# MCU.net
KiCad netlist of a schematic drawn in Altium Designer
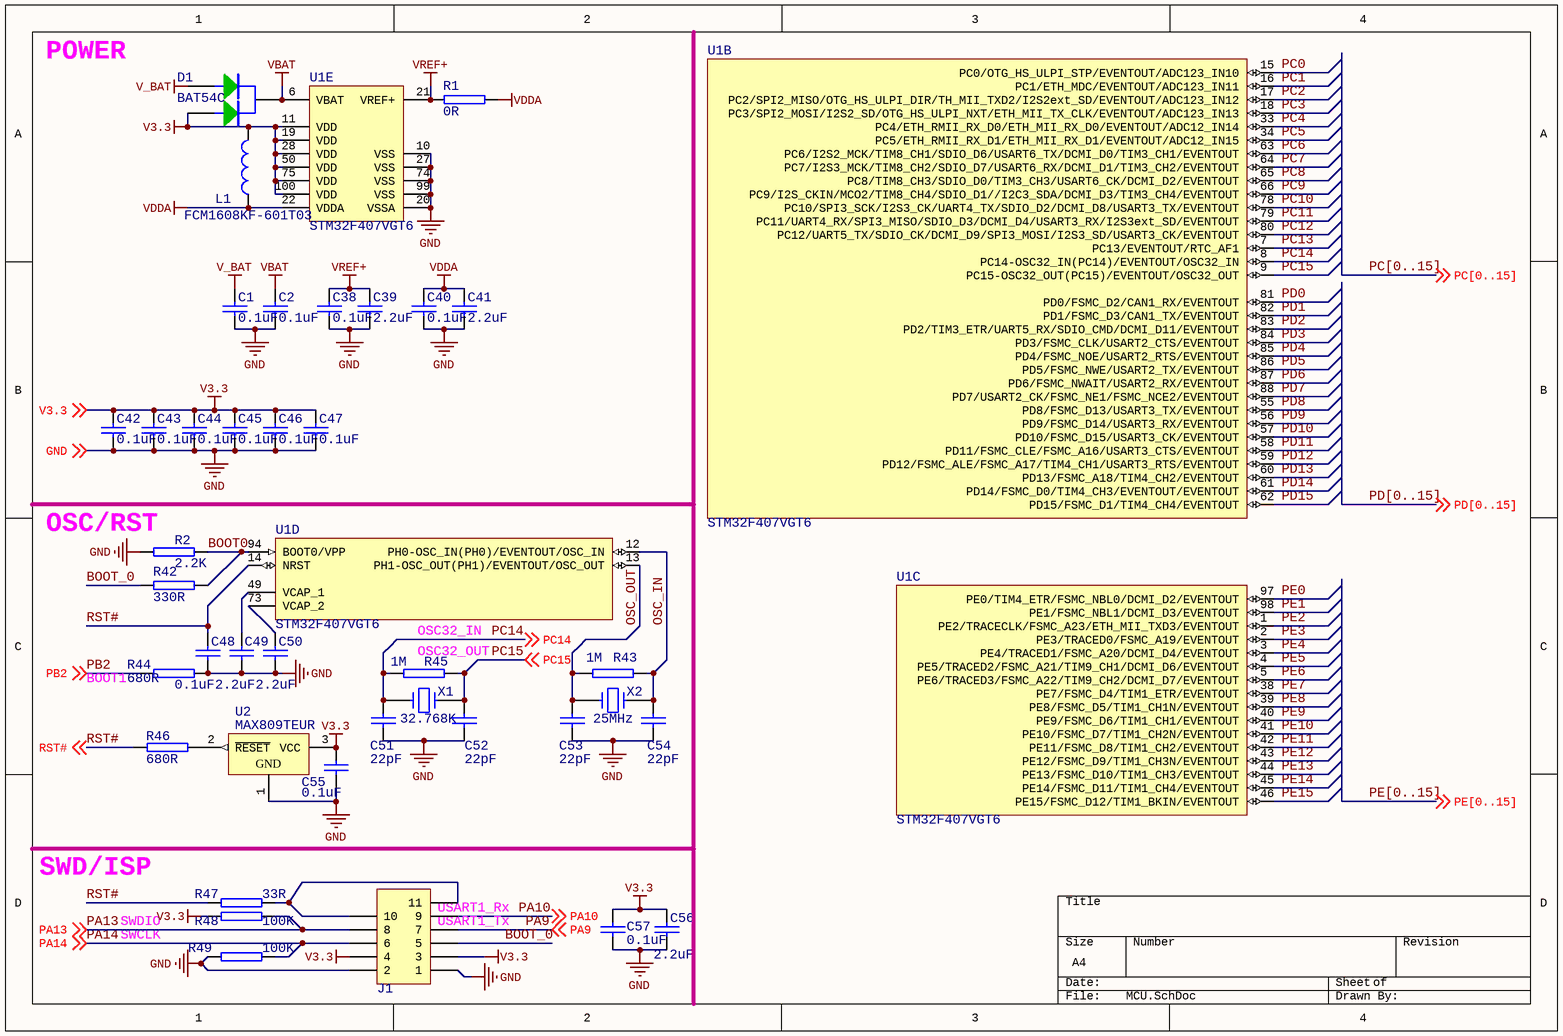
[diagram p0: MCU.SchDoc]

(export (version "E")
  (design (tool "Eeschema 10.0.6"))
  (components
    (comp (ref "C1")
      (value "0.1uF")
      (footprint "C1608(0603)")
      (description "Capacitor")
      (libsource (lib "input") (part "CAP"))
    )
    (comp (ref "C2")
      (value "0.1uF")
      (footprint "C1608(0603)")
      (description "Capacitor")
      (libsource (lib "input") (part "CAP"))
    )
    (comp (ref "C38")
      (value "0.1uF")
      (footprint "C1608(0603)")
      (description "Capacitor")
      (libsource (lib "input") (part "CAP"))
    )
    (comp (ref "C39")
      (value "2.2uF")
      (footprint "C1608(0603)")
      (description "Capacitor")
      (libsource (lib "input") (part "CAP"))
    )
    (comp (ref "C40")
      (value "0.1uF")
      (footprint "C1608(0603)")
      (description "Capacitor")
      (libsource (lib "input") (part "CAP"))
    )
    (comp (ref "C41")
      (value "2.2uF")
      (footprint "C1608(0603)")
      (description "Capacitor")
      (libsource (lib "input") (part "CAP"))
    )
    (comp (ref "C42")
      (value "0.1uF")
      (footprint "C1608(0603)")
      (description "Capacitor")
      (libsource (lib "input") (part "CAP"))
    )
    (comp (ref "C43")
      (value "0.1uF")
      (footprint "C1608(0603)")
      (description "Capacitor")
      (libsource (lib "input") (part "CAP"))
    )
    (comp (ref "C44")
      (value "0.1uF")
      (footprint "C1608(0603)")
      (description "Capacitor")
      (libsource (lib "input") (part "CAP"))
    )
    (comp (ref "C45")
      (value "0.1uF")
      (footprint "C1608(0603)")
      (description "Capacitor")
      (libsource (lib "input") (part "CAP"))
    )
    (comp (ref "C46")
      (value "0.1uF")
      (footprint "C1608(0603)")
      (description "Capacitor")
      (libsource (lib "input") (part "CAP"))
    )
    (comp (ref "C47")
      (value "0.1uF")
      (footprint "C1608(0603)")
      (description "Capacitor")
      (libsource (lib "input") (part "CAP"))
    )
    (comp (ref "C48")
      (value "0.1uF")
      (footprint "C1608(0603)")
      (description "Capacitor")
      (libsource (lib "input") (part "CAP"))
    )
    (comp (ref "C49")
      (value "2.2uF")
      (footprint "C1608(0603)")
      (description "Capacitor")
      (libsource (lib "input") (part "CAP"))
    )
    (comp (ref "C50")
      (value "2.2uF")
      (footprint "C1608(0603)")
      (description "Capacitor")
      (libsource (lib "input") (part "CAP"))
    )
    (comp (ref "C51")
      (value "22pF")
      (footprint "C1608(0603)")
      (description "Capacitor")
      (libsource (lib "input") (part "CAP"))
    )
    (comp (ref "C52")
      (value "22pF")
      (footprint "C1608(0603)")
      (description "Capacitor")
      (libsource (lib "input") (part "CAP"))
    )
    (comp (ref "C53")
      (value "22pF")
      (footprint "C1608(0603)")
      (description "Capacitor")
      (libsource (lib "input") (part "CAP"))
    )
    (comp (ref "C54")
      (value "22pF")
      (footprint "C1608(0603)")
      (description "Capacitor")
      (libsource (lib "input") (part "CAP"))
    )
    (comp (ref "C55")
      (value "0.1uF")
      (footprint "C1608(0603)")
      (description "Capacitor")
      (libsource (lib "input") (part "CAP"))
    )
    (comp (ref "C56")
      (value "2.2uF")
      (footprint "C1608(0603)")
      (description "Capacitor")
      (libsource (lib "input") (part "CAP"))
    )
    (comp (ref "C57")
      (value "0.1uF")
      (footprint "C1608(0603)")
      (description "Capacitor")
      (libsource (lib "input") (part "CAP"))
    )
    (comp (ref "D1")
      (value "BAT54C")
      (footprint "SOT23-3_N")
      (libsource (lib "Mini-STM32F4x9IG-DK-B-SCH") (part "BAT54C"))
    )
    (comp (ref "J1")
      (value "H2.54 6X2")
      (footprint "HDR2X6H")
      (description "Header, 6-Pin, Dual row")
      (fields (field (name "PUBLISHER") "Altium Limited"))
      (libsource (lib "Miscellaneous Connectors") (part "Header 6X2"))
    )
    (comp (ref "L1")
      (value "FCM1608KF-601T03")
      (footprint "R1608(0603)")
      (description "Inductor")
      (fields (field (name "PUBLISHER") "Altium Limited"))
      (libsource (lib "Miscellaneous Devices") (part "Inductor"))
    )
    (comp (ref "R1") (value "0R") (footprint "R1608(0603)") (libsource (lib "motor") (part "R")))
    (comp (ref "R2") (value "2.2K") (footprint "R1608(0603)") (libsource (lib "motor") (part "R")))
    (comp (ref "R42") (value "330R") (footprint "R1608(0603)") (libsource (lib "motor") (part "R")))
    (comp (ref "R43") (value "1M") (footprint "R1608(0603)") (libsource (lib "motor") (part "R")))
    (comp (ref "R44") (value "680R") (footprint "R1608(0603)") (libsource (lib "motor") (part "R")))
    (comp (ref "R45") (value "1M") (footprint "R1608(0603)") (libsource (lib "motor") (part "R")))
    (comp (ref "R46") (value "680R") (footprint "R1608(0603)") (libsource (lib "motor") (part "R")))
    (comp (ref "R47") (value "33R") (footprint "R1608(0603)") (libsource (lib "motor") (part "R")))
    (comp (ref "R48") (value "100K") (footprint "R1608(0603)") (libsource (lib "motor") (part "R")))
    (comp (ref "R49") (value "100K") (footprint "R1608(0603)") (libsource (lib "motor") (part "R")))
    (comp (ref "U1")
      (value "STM32F407VGT6")
      (footprint "TQFP100_N")
      (libsource (lib "STMicroelectronics STM32 F4") (part "STM32F407VGT6"))
    )
    (comp (ref "U2")
      (value "MAX809TEUR")
      (footprint "SOT23-3_N")
      (description "3-Terminal, 1.2V Voltage Reference")
      (fields (field (name "PUBLISHER") "Altium Limited"))
      (libsource (lib "Maxim Power Mgt Voltage Reference") (part "MAX6520EUR-T"))
    )
    (comp (ref "X1") (value "32.768K") (footprint "FC-135") (libsource (lib "input") (part "CRYSTAL")))
    (comp (ref "X2") (value "25MHz") (footprint "XTAL-3225") (libsource (lib "") (part "CRYSTAL_1")))
  )
  (nets
    (net (code "1") (name "/BOOT0") (class "Default")
      (node (ref "R2") (pin "1") (pinfunction "1_1") (pintype "passive"))
      (node (ref "R42") (pin "2") (pinfunction "2_2") (pintype "passive"))
      (node (ref "U1") (pin "94") (pinfunction "BOOT0/VPP_94") (pintype "input"))
    )
    (net (code "2") (name "/BOOT_0") (class "Default")
      (node (ref "J1") (pin "5") (pinfunction "5_5") (pintype "passive"))
      (node (ref "R42") (pin "1") (pinfunction "1_1") (pintype "passive"))
    )
    (net (code "3") (name "/OSC_IN") (class "Default")
      (node (ref "C54") (pin "2") (pinfunction "2_2") (pintype "passive"))
      (node (ref "R43") (pin "1") (pinfunction "1_1") (pintype "passive"))
      (node (ref "U1") (pin "12") (pinfunction "PH0-OSC_IN(PH0)/EVENTOUT/OSC_IN_12") (pintype "bidirectional"))
      (node (ref "X2") (pin "1") (pinfunction "1_1") (pintype "passive"))
    )
    (net (code "4") (name "/OSC_OUT") (class "Default")
      (node (ref "C53") (pin "2") (pinfunction "2_2") (pintype "passive"))
      (node (ref "R43") (pin "2") (pinfunction "2_2") (pintype "passive"))
      (node (ref "U1") (pin "13") (pinfunction "PH1-OSC_OUT(PH1)/EVENTOUT/OSC_OUT_13") (pintype "bidirectional"))
      (node (ref "X2") (pin "3") (pinfunction "3_3") (pintype "passive"))
    )
    (net (code "5") (name "GND") (class "Default")
      (node (ref "C1") (pin "2") (pinfunction "2_2") (pintype "passive"))
      (node (ref "C2") (pin "2") (pinfunction "2_2") (pintype "passive"))
      (node (ref "C38") (pin "2") (pinfunction "2_2") (pintype "passive"))
      (node (ref "C39") (pin "2") (pinfunction "2_2") (pintype "passive"))
      (node (ref "C40") (pin "2") (pinfunction "2_2") (pintype "passive"))
      (node (ref "C41") (pin "2") (pinfunction "2_2") (pintype "passive"))
      (node (ref "C42") (pin "2") (pinfunction "2_2") (pintype "passive"))
      (node (ref "C43") (pin "2") (pinfunction "2_2") (pintype "passive"))
      (node (ref "C44") (pin "2") (pinfunction "2_2") (pintype "passive"))
      (node (ref "C45") (pin "2") (pinfunction "2_2") (pintype "passive"))
      (node (ref "C46") (pin "2") (pinfunction "2_2") (pintype "passive"))
      (node (ref "C47") (pin "2") (pinfunction "2_2") (pintype "passive"))
      (node (ref "C48") (pin "2") (pinfunction "2_2") (pintype "passive"))
      (node (ref "C49") (pin "2") (pinfunction "2_2") (pintype "passive"))
      (node (ref "C50") (pin "2") (pinfunction "2_2") (pintype "passive"))
      (node (ref "C51") (pin "1") (pinfunction "1_1") (pintype "passive"))
      (node (ref "C52") (pin "1") (pinfunction "1_1") (pintype "passive"))
      (node (ref "C53") (pin "1") (pinfunction "1_1") (pintype "passive"))
      (node (ref "C54") (pin "1") (pinfunction "1_1") (pintype "passive"))
      (node (ref "C55") (pin "2") (pinfunction "2_2") (pintype "passive"))
      (node (ref "C56") (pin "2") (pinfunction "2_2") (pintype "passive"))
      (node (ref "C57") (pin "1") (pinfunction "1_1") (pintype "passive"))
      (node (ref "J1") (pin "1") (pinfunction "1_1") (pintype "passive"))
      (node (ref "J1") (pin "2") (pinfunction "2_2") (pintype "passive"))
      (node (ref "R2") (pin "2") (pinfunction "2_2") (pintype "passive"))
      (node (ref "R44") (pin "1") (pinfunction "1_1") (pintype "passive"))
      (node (ref "R49") (pin "1") (pinfunction "1_1") (pintype "passive"))
      (node (ref "U1") (pin "10") (pinfunction "VSS_10") (pintype "power_in"))
      (node (ref "U1") (pin "20") (pinfunction "VSSA_20") (pintype "power_in"))
      (node (ref "U1") (pin "27") (pinfunction "VSS_27") (pintype "power_in"))
      (node (ref "U1") (pin "74") (pinfunction "VSS_74") (pintype "power_in"))
      (node (ref "U1") (pin "99") (pinfunction "VSS_99") (pintype "power_in"))
      (node (ref "U2") (pin "1") (pinfunction "GND_1") (pintype "power_in"))
    )
    (net (code "6") (name "Net-(J1-Pad10)") (class "Default")
      (node (ref "J1") (pin "10") (pinfunction "10_10") (pintype "passive"))
      (node (ref "J1") (pin "11") (pinfunction "11_11") (pintype "passive"))
      (node (ref "R47") (pin "1") (pinfunction "1_1") (pintype "passive"))
    )
    (net (code "7") (name "Net-(U1D-VCAP_1)") (class "Default")
      (node (ref "C49") (pin "1") (pinfunction "1_1") (pintype "passive"))
      (node (ref "U1") (pin "49") (pinfunction "VCAP_1_49") (pintype "power_in"))
    )
    (net (code "8") (name "Net-(U1D-VCAP_2)") (class "Default")
      (node (ref "C50") (pin "1") (pinfunction "1_1") (pintype "passive"))
      (node (ref "U1") (pin "73") (pinfunction "VCAP_2_73") (pintype "power_in"))
    )
    (net (code "9") (name "Net-(U2-~{RESET})") (class "Default")
      (node (ref "R46") (pin "2") (pinfunction "2_2") (pintype "passive"))
      (node (ref "U2") (pin "2") (pinfunction "~{RESET}_2") (pintype "output"))
    )
    (net (code "10") (name "PA9") (class "Default")
      (node (ref "J1") (pin "7") (pinfunction "7_7") (pintype "passive"))
    )
    (net (code "11") (name "PA10") (class "Default")
      (node (ref "J1") (pin "9") (pinfunction "9_9") (pintype "passive"))
    )
    (net (code "12") (name "PA13") (class "Default")
      (node (ref "J1") (pin "8") (pinfunction "8_8") (pintype "passive"))
      (node (ref "R48") (pin "2") (pinfunction "2_2") (pintype "passive"))
    )
    (net (code "13") (name "PA14") (class "Default")
      (node (ref "J1") (pin "6") (pinfunction "6_6") (pintype "passive"))
      (node (ref "R49") (pin "2") (pinfunction "2_2") (pintype "passive"))
    )
    (net (code "14") (name "PB2") (class "Default")
      (node (ref "R44") (pin "2") (pinfunction "2_2") (pintype "passive"))
    )
    (net (code "15") (name "PC0") (class "Default")
      (node (ref "U1") (pin "15") (pinfunction "PC0/OTG_HS_ULPI_STP/EVENTOUT/ADC123_IN10_15") (pintype "bidirectional"))
    )
    (net (code "16") (name "PC1") (class "Default")
      (node (ref "U1") (pin "16") (pinfunction "PC1/ETH_MDC/EVENTOUT/ADC123_IN11_16") (pintype "bidirectional"))
    )
    (net (code "17") (name "PC2") (class "Default")
      (node (ref "U1") (pin "17") (pinfunction "PC2/SPI2_MISO/OTG_HS_ULPI_DIR/TH_MII_TXD2/I2S2ext_SD/EVENTOUT/ADC123_IN12_17") (pintype "bidirectional"))
    )
    (net (code "18") (name "PC3") (class "Default")
      (node (ref "U1") (pin "18") (pinfunction "PC3/SPI2_MOSI/I2S2_SD/OTG_HS_ULPI_NXT/ETH_MII_TX_CLK/EVENTOUT/ADC123_IN13_18") (pintype "bidirectional"))
    )
    (net (code "19") (name "PC4") (class "Default")
      (node (ref "U1") (pin "33") (pinfunction "PC4/ETH_RMII_RX_D0/ETH_MII_RX_D0/EVENTOUT/ADC12_IN14_33") (pintype "bidirectional"))
    )
    (net (code "20") (name "PC5") (class "Default")
      (node (ref "U1") (pin "34") (pinfunction "PC5/ETH_RMII_RX_D1/ETH_MII_RX_D1/EVENTOUT/ADC12_IN15_34") (pintype "bidirectional"))
    )
    (net (code "21") (name "PC6") (class "Default")
      (node (ref "U1") (pin "63") (pinfunction "PC6/I2S2_MCK/TIM8_CH1/SDIO_D6/USART6_TX/DCMI_D0/TIM3_CH1/EVENTOUT_63") (pintype "bidirectional"))
    )
    (net (code "22") (name "PC7") (class "Default")
      (node (ref "U1") (pin "64") (pinfunction "PC7/I2S3_MCK/TIM8_CH2/SDIO_D7/USART6_RX/DCMI_D1/TIM3_CH2/EVENTOUT_64") (pintype "bidirectional"))
    )
    (net (code "23") (name "PC8") (class "Default")
      (node (ref "U1") (pin "65") (pinfunction "PC8/TIM8_CH3/SDIO_D0/TIM3_CH3/USART6_CK/DCMI_D2/EVENTOUT_65") (pintype "bidirectional"))
    )
    (net (code "24") (name "PC9") (class "Default")
      (node (ref "U1") (pin "66") (pinfunction "PC9/I2S_CKIN/MCO2/TIM8_CH4/SDIO_D1//I2C3_SDA/DCMI_D3/TIM3_CH4/EVENTOUT_66") (pintype "bidirectional"))
    )
    (net (code "25") (name "PC10") (class "Default")
      (node (ref "U1") (pin "78") (pinfunction "PC10/SPI3_SCK/I2S3_CK/UART4_TX/SDIO_D2/DCMI_D8/USART3_TX/EVENTOUT_78") (pintype "bidirectional"))
    )
    (net (code "26") (name "PC11") (class "Default")
      (node (ref "U1") (pin "79") (pinfunction "PC11/UART4_RX/SPI3_MISO/SDIO_D3/DCMI_D4/USART3_RX/I2S3ext_SD/EVENTOUT_79") (pintype "bidirectional"))
    )
    (net (code "27") (name "PC12") (class "Default")
      (node (ref "U1") (pin "80") (pinfunction "PC12/UART5_TX/SDIO_CK/DCMI_D9/SPI3_MOSI/I2S3_SD/USART3_CK/EVENTOUT_80") (pintype "bidirectional"))
    )
    (net (code "28") (name "PC13") (class "Default")
      (node (ref "U1") (pin "7") (pinfunction "PC13/EVENTOUT/RTC_AF1_7") (pintype "bidirectional"))
    )
    (net (code "29") (name "PC14") (class "Default")
      (node (ref "C51") (pin "2") (pinfunction "2_2") (pintype "passive"))
      (node (ref "R45") (pin "2") (pinfunction "2_2") (pintype "passive"))
      (node (ref "U1") (pin "8") (pinfunction "PC14-OSC32_IN(PC14)/EVENTOUT/OSC32_IN_8") (pintype "bidirectional"))
      (node (ref "X1") (pin "2") (pinfunction "2_2") (pintype "passive"))
    )
    (net (code "30") (name "PC15") (class "Default")
      (node (ref "C52") (pin "2") (pinfunction "2_2") (pintype "passive"))
      (node (ref "R45") (pin "1") (pinfunction "1_1") (pintype "passive"))
      (node (ref "U1") (pin "9") (pinfunction "PC15-OSC32_OUT(PC15)/EVENTOUT/OSC32_OUT_9") (pintype "bidirectional"))
      (node (ref "X1") (pin "1") (pinfunction "1_1") (pintype "passive"))
    )
    (net (code "32") (name "PD0") (class "Default")
      (node (ref "U1") (pin "81") (pinfunction "PD0/FSMC_D2/CAN1_RX/EVENTOUT_81") (pintype "bidirectional"))
    )
    (net (code "33") (name "PD1") (class "Default")
      (node (ref "U1") (pin "82") (pinfunction "PD1/FSMC_D3/CAN1_TX/EVENTOUT_82") (pintype "bidirectional"))
    )
    (net (code "34") (name "PD2") (class "Default")
      (node (ref "U1") (pin "83") (pinfunction "PD2/TIM3_ETR/UART5_RX/SDIO_CMD/DCMI_D11/EVENTOUT_83") (pintype "bidirectional"))
    )
    (net (code "35") (name "PD3") (class "Default")
      (node (ref "U1") (pin "84") (pinfunction "PD3/FSMC_CLK/USART2_CTS/EVENTOUT_84") (pintype "bidirectional"))
    )
    (net (code "36") (name "PD4") (class "Default")
      (node (ref "U1") (pin "85") (pinfunction "PD4/FSMC_NOE/USART2_RTS/EVENTOUT_85") (pintype "bidirectional"))
    )
    (net (code "37") (name "PD5") (class "Default")
      (node (ref "U1") (pin "86") (pinfunction "PD5/FSMC_NWE/USART2_TX/EVENTOUT_86") (pintype "bidirectional"))
    )
    (net (code "38") (name "PD6") (class "Default")
      (node (ref "U1") (pin "87") (pinfunction "PD6/FSMC_NWAIT/USART2_RX/EVENTOUT_87") (pintype "bidirectional"))
    )
    (net (code "39") (name "PD7") (class "Default")
      (node (ref "U1") (pin "88") (pinfunction "PD7/USART2_CK/FSMC_NE1/FSMC_NCE2/EVENTOUT_88") (pintype "bidirectional"))
    )
    (net (code "40") (name "PD8") (class "Default")
      (node (ref "U1") (pin "55") (pinfunction "PD8/FSMC_D13/USART3_TX/EVENTOUT_55") (pintype "bidirectional"))
    )
    (net (code "41") (name "PD9") (class "Default")
      (node (ref "U1") (pin "56") (pinfunction "PD9/FSMC_D14/USART3_RX/EVENTOUT_56") (pintype "bidirectional"))
    )
    (net (code "42") (name "PD10") (class "Default")
      (node (ref "U1") (pin "57") (pinfunction "PD10/FSMC_D15/USART3_CK/EVENTOUT_57") (pintype "bidirectional"))
    )
    (net (code "43") (name "PD11") (class "Default")
      (node (ref "U1") (pin "58") (pinfunction "PD11/FSMC_CLE/FSMC_A16/USART3_CTS/EVENTOUT_58") (pintype "bidirectional"))
    )
    (net (code "44") (name "PD12") (class "Default")
      (node (ref "U1") (pin "59") (pinfunction "PD12/FSMC_ALE/FSMC_A17/TIM4_CH1/USART3_RTS/EVENTOUT_59") (pintype "bidirectional"))
    )
    (net (code "45") (name "PD13") (class "Default")
      (node (ref "U1") (pin "60") (pinfunction "PD13/FSMC_A18/TIM4_CH2/EVENTOUT_60") (pintype "bidirectional"))
    )
    (net (code "46") (name "PD14") (class "Default")
      (node (ref "U1") (pin "61") (pinfunction "PD14/FSMC_D0/TIM4_CH3/EVENTOUT/EVENTOUT_61") (pintype "bidirectional"))
    )
    (net (code "47") (name "PD15") (class "Default")
      (node (ref "U1") (pin "62") (pinfunction "PD15/FSMC_D1/TIM4_CH4/EVENTOUT_62") (pintype "bidirectional"))
    )
    (net (code "49") (name "PE0") (class "Default")
      (node (ref "U1") (pin "97") (pinfunction "PE0/TIM4_ETR/FSMC_NBL0/DCMI_D2/EVENTOUT_97") (pintype "bidirectional"))
    )
    (net (code "50") (name "PE1") (class "Default")
      (node (ref "U1") (pin "98") (pinfunction "PE1/FSMC_NBL1/DCMI_D3/EVENTOUT_98") (pintype "bidirectional"))
    )
    (net (code "51") (name "PE2") (class "Default")
      (node (ref "U1") (pin "1") (pinfunction "PE2/TRACECLK/FSMC_A23/ETH_MII_TXD3/EVENTOUT_1") (pintype "bidirectional"))
    )
    (net (code "52") (name "PE3") (class "Default")
      (node (ref "U1") (pin "2") (pinfunction "PE3/TRACED0/FSMC_A19/EVENTOUT_2") (pintype "bidirectional"))
    )
    (net (code "53") (name "PE4") (class "Default")
      (node (ref "U1") (pin "3") (pinfunction "PE4/TRACED1/FSMC_A20/DCMI_D4/EVENTOUT_3") (pintype "bidirectional"))
    )
    (net (code "54") (name "PE5") (class "Default")
      (node (ref "U1") (pin "4") (pinfunction "PE5/TRACED2/FSMC_A21/TIM9_CH1/DCMI_D6/EVENTOUT_4") (pintype "bidirectional"))
    )
    (net (code "55") (name "PE6") (class "Default")
      (node (ref "U1") (pin "5") (pinfunction "PE6/TRACED3/FSMC_A22/TIM9_CH2/DCMI_D7/EVENTOUT_5") (pintype "bidirectional"))
    )
    (net (code "56") (name "PE7") (class "Default")
      (node (ref "U1") (pin "38") (pinfunction "PE7/FSMC_D4/TIM1_ETR/EVENTOUT_38") (pintype "bidirectional"))
    )
    (net (code "57") (name "PE8") (class "Default")
      (node (ref "U1") (pin "39") (pinfunction "PE8/FSMC_D5/TIM1_CH1N/EVENTOUT_39") (pintype "bidirectional"))
    )
    (net (code "58") (name "PE9") (class "Default")
      (node (ref "U1") (pin "40") (pinfunction "PE9/FSMC_D6/TIM1_CH1/EVENTOUT_40") (pintype "bidirectional"))
    )
    (net (code "59") (name "PE10") (class "Default")
      (node (ref "U1") (pin "41") (pinfunction "PE10/FSMC_D7/TIM1_CH2N/EVENTOUT_41") (pintype "bidirectional"))
    )
    (net (code "60") (name "PE11") (class "Default")
      (node (ref "U1") (pin "42") (pinfunction "PE11/FSMC_D8/TIM1_CH2/EVENTOUT_42") (pintype "bidirectional"))
    )
    (net (code "61") (name "PE12") (class "Default")
      (node (ref "U1") (pin "43") (pinfunction "PE12/FSMC_D9/TIM1_CH3N/EVENTOUT_43") (pintype "bidirectional"))
    )
    (net (code "62") (name "PE13") (class "Default")
      (node (ref "U1") (pin "44") (pinfunction "PE13/FSMC_D10/TIM1_CH3/EVENTOUT_44") (pintype "bidirectional"))
    )
    (net (code "63") (name "PE14") (class "Default")
      (node (ref "U1") (pin "45") (pinfunction "PE14/FSMC_D11/TIM1_CH4/EVENTOUT_45") (pintype "bidirectional"))
    )
    (net (code "64") (name "PE15") (class "Default")
      (node (ref "U1") (pin "46") (pinfunction "PE15/FSMC_D12/TIM1_BKIN/EVENTOUT_46") (pintype "bidirectional"))
    )
    (net (code "66") (name "RST#") (class "Default")
      (node (ref "C48") (pin "1") (pinfunction "1_1") (pintype "passive"))
      (node (ref "R46") (pin "1") (pinfunction "1_1") (pintype "passive"))
      (node (ref "R47") (pin "2") (pinfunction "2_2") (pintype "passive"))
      (node (ref "U1") (pin "14") (pinfunction "NRST_14") (pintype "bidirectional"))
    )
    (net (code "67") (name "V3.3") (class "Default")
      (node (ref "C42") (pin "1") (pinfunction "1_1") (pintype "passive"))
      (node (ref "C43") (pin "1") (pinfunction "1_1") (pintype "passive"))
      (node (ref "C44") (pin "1") (pinfunction "1_1") (pintype "passive"))
      (node (ref "C45") (pin "1") (pinfunction "1_1") (pintype "passive"))
      (node (ref "C46") (pin "1") (pinfunction "1_1") (pintype "passive"))
      (node (ref "C47") (pin "1") (pinfunction "1_1") (pintype "passive"))
      (node (ref "C55") (pin "1") (pinfunction "1_1") (pintype "passive"))
      (node (ref "C56") (pin "1") (pinfunction "1_1") (pintype "passive"))
      (node (ref "C57") (pin "2") (pinfunction "2_2") (pintype "passive"))
      (node (ref "D1") (pin "1") (pinfunction "1_1") (pintype "passive"))
      (node (ref "J1") (pin "3") (pinfunction "3_3") (pintype "passive"))
      (node (ref "J1") (pin "4") (pinfunction "4_4") (pintype "passive"))
      (node (ref "L1") (pin "2") (pinfunction "2_2") (pintype "passive"))
      (node (ref "R48") (pin "1") (pinfunction "1_1") (pintype "passive"))
      (node (ref "U1") (pin "100") (pinfunction "VDD_100") (pintype "power_in"))
      (node (ref "U1") (pin "11") (pinfunction "VDD_11") (pintype "power_in"))
      (node (ref "U1") (pin "19") (pinfunction "VDD_19") (pintype "power_in"))
      (node (ref "U1") (pin "28") (pinfunction "VDD_28") (pintype "power_in"))
      (node (ref "U1") (pin "50") (pinfunction "VDD_50") (pintype "power_in"))
      (node (ref "U1") (pin "75") (pinfunction "VDD_75") (pintype "power_in"))
      (node (ref "U2") (pin "3") (pinfunction "VCC_3") (pintype "power_in"))
    )
    (net (code "68") (name "VBAT") (class "Default")
      (node (ref "C2") (pin "1") (pinfunction "1_1") (pintype "passive"))
      (node (ref "D1") (pin "3") (pinfunction "3_3") (pintype "passive"))
      (node (ref "U1") (pin "6") (pinfunction "VBAT_6") (pintype "power_in"))
    )
    (net (code "69") (name "VDDA") (class "Default")
      (node (ref "C40") (pin "1") (pinfunction "1_1") (pintype "passive"))
      (node (ref "C41") (pin "1") (pinfunction "1_1") (pintype "passive"))
      (node (ref "L1") (pin "1") (pinfunction "1_1") (pintype "passive"))
      (node (ref "R1") (pin "1") (pinfunction "1_1") (pintype "passive"))
      (node (ref "U1") (pin "22") (pinfunction "VDDA_22") (pintype "power_in"))
    )
    (net (code "70") (name "VREF+") (class "Default")
      (node (ref "C38") (pin "1") (pinfunction "1_1") (pintype "passive"))
      (node (ref "C39") (pin "1") (pinfunction "1_1") (pintype "passive"))
      (node (ref "R1") (pin "2") (pinfunction "2_2") (pintype "passive"))
      (node (ref "U1") (pin "21") (pinfunction "VREF+_21") (pintype "power_in"))
    )
    (net (code "71") (name "V_BAT") (class "Default")
      (node (ref "C1") (pin "1") (pinfunction "1_1") (pintype "passive"))
      (node (ref "D1") (pin "2") (pinfunction "2_2") (pintype "passive"))
    )
  )
)
